# LB_BIT_i36_MICROSEQUENCER-v03_6_7.net
KiCad netlist of a schematic drawn in EAGLE
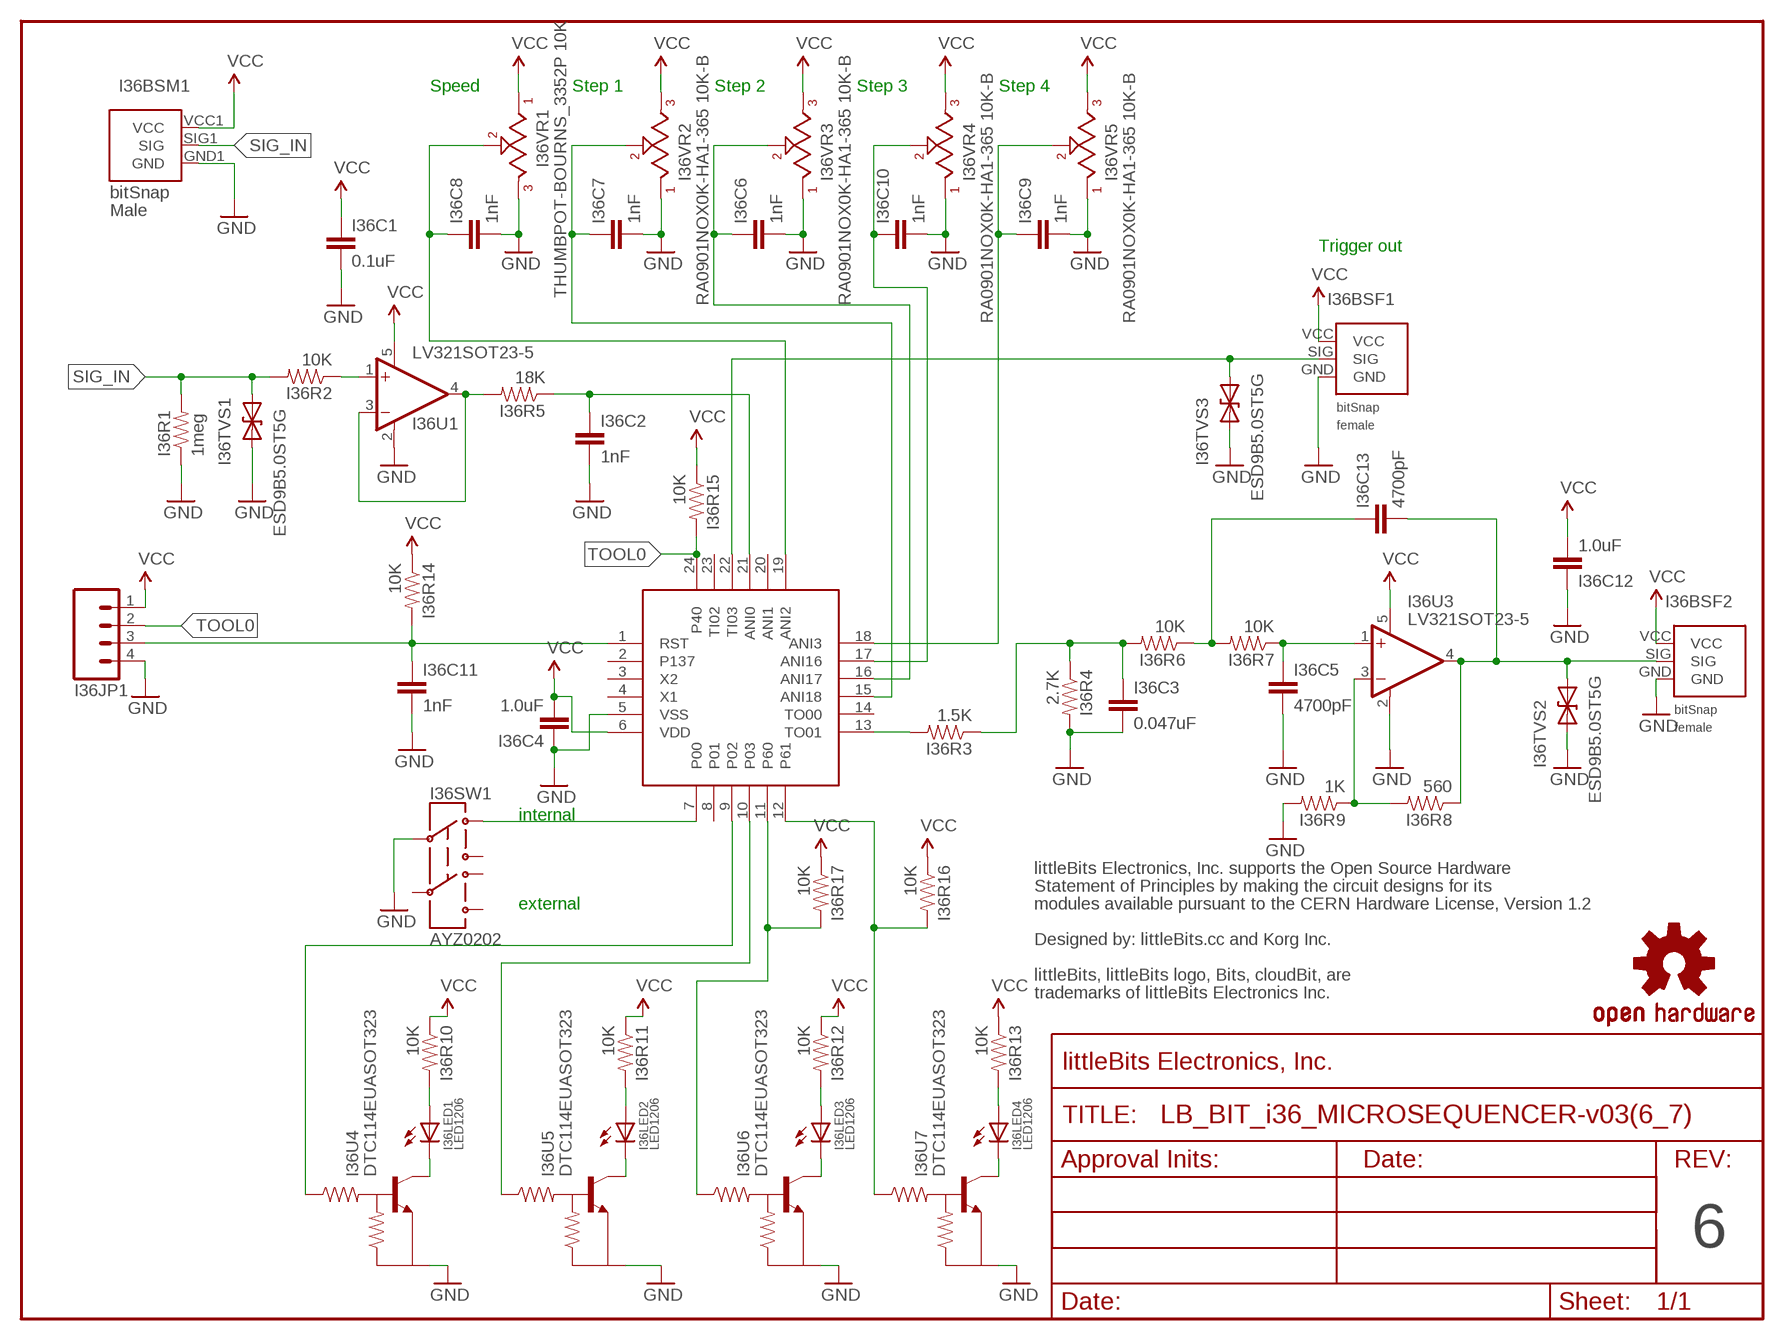
[diagram p0: schematic, sheet 1]

(export (version "E")
  (design (tool "Eeschema 10.0.6"))
  (components
    (comp (ref "I36BSF1")
      (value "BITSNAP_V03_FEMALE")
      (footprint "eagle-import:BITSNAP_V03_FEMALE")
      (libsource (lib "eagle-import") (part "BITSNAP_V03_FEMALE"))
    )
    (comp (ref "I36BSF2")
      (value "BITSNAP_V03_FEMALE")
      (footprint "eagle-import:BITSNAP_V03_FEMALE")
      (libsource (lib "eagle-import") (part "BITSNAP_V03_FEMALE"))
    )
    (comp (ref "I36BSM1")
      (value "BITSNAP_V03_MALE")
      (footprint "eagle-import:BITSNAP_V03_MALE")
      (libsource (lib "eagle-import") (part "BITSNAP_V03_MALE"))
    )
    (comp (ref "I36C1")
      (value "0.1uF")
      (footprint "eagle-import:CAP-0603")
      (libsource (lib "eagle-import") (part "CAPCAP-0603"))
    )
    (comp (ref "I36C2")
      (value "1nF")
      (footprint "eagle-import:CAP-0603")
      (libsource (lib "eagle-import") (part "CAPCAP-0603"))
    )
    (comp (ref "I36C3")
      (value "0.047uF")
      (footprint "eagle-import:CAP-0603")
      (libsource (lib "eagle-import") (part "CAPCAP-0603"))
    )
    (comp (ref "I36C4")
      (value "1.0uF")
      (footprint "eagle-import:CAP-0603")
      (libsource (lib "eagle-import") (part "CAPCAP-0603"))
    )
    (comp (ref "I36C5")
      (value "4700pF")
      (footprint "eagle-import:CAP-0603")
      (libsource (lib "eagle-import") (part "CAPCAP-0603"))
    )
    (comp (ref "I36C6")
      (value "1nF")
      (footprint "eagle-import:CAP-0603")
      (libsource (lib "eagle-import") (part "CAPCAP-0603"))
    )
    (comp (ref "I36C7")
      (value "1nF")
      (footprint "eagle-import:CAP-0603")
      (libsource (lib "eagle-import") (part "CAPCAP-0603"))
    )
    (comp (ref "I36C8")
      (value "1nF")
      (footprint "eagle-import:CAP-0603")
      (libsource (lib "eagle-import") (part "CAPCAP-0603"))
    )
    (comp (ref "I36C9")
      (value "1nF")
      (footprint "eagle-import:CAP-0603")
      (libsource (lib "eagle-import") (part "CAPCAP-0603"))
    )
    (comp (ref "I36C10")
      (value "1nF")
      (footprint "eagle-import:CAP-0603")
      (libsource (lib "eagle-import") (part "CAPCAP-0603"))
    )
    (comp (ref "I36C11")
      (value "1nF")
      (footprint "eagle-import:CAP-0603")
      (libsource (lib "eagle-import") (part "CAPCAP-0603"))
    )
    (comp (ref "I36C12")
      (value "1.0uF")
      (footprint "eagle-import:CAP-0603")
      (libsource (lib "eagle-import") (part "CAPCAP-0603"))
    )
    (comp (ref "I36C13")
      (value "4700pF")
      (footprint "eagle-import:CAP-0603")
      (libsource (lib "eagle-import") (part "CAPCAP-0603"))
    )
    (comp (ref "I36JP1")
      (value "HDR-4SM_SML")
      (footprint "eagle-import:SIP4-SM-0.1IN-NOS.S.")
      (libsource (lib "eagle-import") (part "HDR-4SM_SML"))
    )
    (comp (ref "I36LED1")
      (value "LED1206")
      (footprint "eagle-import:LED-1206")
      (libsource (lib "eagle-import") (part "LED1206"))
    )
    (comp (ref "I36LED2")
      (value "LED1206")
      (footprint "eagle-import:LED-1206")
      (libsource (lib "eagle-import") (part "LED1206"))
    )
    (comp (ref "I36LED3")
      (value "LED1206")
      (footprint "eagle-import:LED-1206")
      (libsource (lib "eagle-import") (part "LED1206"))
    )
    (comp (ref "I36LED4")
      (value "LED1206")
      (footprint "eagle-import:LED-1206")
      (libsource (lib "eagle-import") (part "LED1206"))
    )
    (comp (ref "I36R1")
      (value "1meg")
      (footprint "eagle-import:RES-0603")
      (libsource (lib "eagle-import") (part "RESISTOR0603"))
    )
    (comp (ref "I36R2")
      (value "10K")
      (footprint "eagle-import:RES-0603")
      (libsource (lib "eagle-import") (part "RESISTOR0603"))
    )
    (comp (ref "I36R3")
      (value "1.5K")
      (footprint "eagle-import:RES-0603")
      (libsource (lib "eagle-import") (part "RESISTOR0603"))
    )
    (comp (ref "I36R4")
      (value "2.7K")
      (footprint "eagle-import:RES-0603")
      (libsource (lib "eagle-import") (part "RESISTOR0603"))
    )
    (comp (ref "I36R5")
      (value "18K")
      (footprint "eagle-import:RES-0603")
      (libsource (lib "eagle-import") (part "RESISTOR0603"))
    )
    (comp (ref "I36R6")
      (value "10K")
      (footprint "eagle-import:RES-0603")
      (libsource (lib "eagle-import") (part "RESISTOR0603"))
    )
    (comp (ref "I36R7")
      (value "10K")
      (footprint "eagle-import:RES-0603")
      (libsource (lib "eagle-import") (part "RESISTOR0603"))
    )
    (comp (ref "I36R8")
      (value "560")
      (footprint "eagle-import:RES-0603")
      (libsource (lib "eagle-import") (part "RESISTOR0603"))
    )
    (comp (ref "I36R9")
      (value "1K")
      (footprint "eagle-import:RES-0603")
      (libsource (lib "eagle-import") (part "RESISTOR0603"))
    )
    (comp (ref "I36R10")
      (value "10K")
      (footprint "eagle-import:RES-0603")
      (libsource (lib "eagle-import") (part "RESISTOR0603"))
    )
    (comp (ref "I36R11")
      (value "10K")
      (footprint "eagle-import:RES-0603")
      (libsource (lib "eagle-import") (part "RESISTOR0603"))
    )
    (comp (ref "I36R12")
      (value "10K")
      (footprint "eagle-import:RES-0603")
      (libsource (lib "eagle-import") (part "RESISTOR0603"))
    )
    (comp (ref "I36R13")
      (value "10K")
      (footprint "eagle-import:RES-0603")
      (libsource (lib "eagle-import") (part "RESISTOR0603"))
    )
    (comp (ref "I36R14")
      (value "10K")
      (footprint "eagle-import:RES-0603")
      (libsource (lib "eagle-import") (part "RESISTOR0603"))
    )
    (comp (ref "I36R15")
      (value "10K")
      (footprint "eagle-import:RES-0603")
      (libsource (lib "eagle-import") (part "RESISTOR0603"))
    )
    (comp (ref "I36R16")
      (value "10K")
      (footprint "eagle-import:RES-0603")
      (libsource (lib "eagle-import") (part "RESISTOR0603"))
    )
    (comp (ref "I36R17")
      (value "10K")
      (footprint "eagle-import:RES-0603")
      (libsource (lib "eagle-import") (part "RESISTOR0603"))
    )
    (comp (ref "I36SW1")
      (value "AYZ0202")
      (footprint "eagle-import:AYZ0202")
      (libsource (lib "eagle-import") (part "AYZ0202"))
    )
    (comp (ref "I36TVS1")
      (value "ESD9B5.0ST5G")
      (footprint "eagle-import:SOD-923")
      (libsource (lib "eagle-import") (part "DIODE-TVSSOD-923"))
    )
    (comp (ref "I36TVS2")
      (value "ESD9B5.0ST5G")
      (footprint "eagle-import:SOD-923")
      (libsource (lib "eagle-import") (part "DIODE-TVSSOD-923"))
    )
    (comp (ref "I36TVS3")
      (value "ESD9B5.0ST5G")
      (footprint "eagle-import:SOD-923")
      (libsource (lib "eagle-import") (part "DIODE-TVSSOD-923"))
    )
    (comp (ref "I36U1")
      (value "LV321SOT23-5")
      (footprint "eagle-import:SOT23-5")
      (libsource (lib "eagle-import") (part "LV321SOT23-5"))
    )
    (comp (ref "I36U2")
      (value "R5F10278QFN-24")
      (footprint "eagle-import:QFN-24(4MM)")
      (libsource (lib "eagle-import") (part "R5F10278QFN-24"))
    )
    (comp (ref "I36U3")
      (value "LV321SOT23-5")
      (footprint "eagle-import:SOT23-5")
      (libsource (lib "eagle-import") (part "LV321SOT23-5"))
    )
    (comp (ref "I36U4")
      (value "DTC114EUASOT323")
      (footprint "eagle-import:SOT323")
      (libsource (lib "eagle-import") (part "DTC114EUASOT323"))
    )
    (comp (ref "I36U5")
      (value "DTC114EUASOT323")
      (footprint "eagle-import:SOT323")
      (libsource (lib "eagle-import") (part "DTC114EUASOT323"))
    )
    (comp (ref "I36U6")
      (value "DTC114EUASOT323")
      (footprint "eagle-import:SOT323")
      (libsource (lib "eagle-import") (part "DTC114EUASOT323"))
    )
    (comp (ref "I36U7")
      (value "DTC114EUASOT323")
      (footprint "eagle-import:SOT323")
      (libsource (lib "eagle-import") (part "DTC114EUASOT323"))
    )
    (comp (ref "I36VR1")
      (value "THUMBPOT-BOURNS_3352P 10K")
      (footprint "eagle-import:THUMBPOT-BOURNS_3352")
      (libsource (lib "eagle-import") (part "THUMBPOT-BOURNS_3352P"))
    )
    (comp (ref "I36VR2")
      (value "RA0901NOX0K-HA1-365 10K-B")
      (footprint "eagle-import:ALPS_POT")
      (libsource (lib "eagle-import") (part "ALPS_POTTH"))
    )
    (comp (ref "I36VR3")
      (value "RA0901NOX0K-HA1-365 10K-B")
      (footprint "eagle-import:ALPS_POT")
      (libsource (lib "eagle-import") (part "ALPS_POTTH"))
    )
    (comp (ref "I36VR4")
      (value "RA0901NOX0K-HA1-365 10K-B")
      (footprint "eagle-import:ALPS_POT")
      (libsource (lib "eagle-import") (part "ALPS_POTTH"))
    )
    (comp (ref "I36VR5")
      (value "RA0901NOX0K-HA1-365 10K-B")
      (footprint "eagle-import:ALPS_POT")
      (libsource (lib "eagle-import") (part "ALPS_POTTH"))
    )
    (comp (ref "U$1")
      (value "OSHWCREDIT-KORG")
      (footprint "eagle-import:OSHWCREDIT-KORG")
      (libsource (lib "eagle-import") (part "OSHWCREDIT-KORG"))
    )
    (comp (ref "U$2")
      (value "OSHW-LOGOL")
      (footprint "eagle-import:OSHW-LOGO-L")
      (libsource (lib "eagle-import") (part "OSHW-LOGOL"))
    )
    (comp (ref "U$3")
      (value "FRAME-LETTER-OHWOHW")
      (footprint "eagle-import:FABDWG01-OHW")
      (libsource (lib "eagle-import") (part "FRAME-LETTER-OHWOHW"))
    )
  )
  (nets
    (net (code "1") (name "GND") (class "Default")
      (node (ref "I36BSF1") (pin "GND") (pinfunction "GND_GND") (pintype "bidirectional"))
      (node (ref "I36BSF2") (pin "GND") (pinfunction "GND_GND") (pintype "bidirectional"))
      (node (ref "I36BSM1") (pin "GND1") (pinfunction "GND_GND1") (pintype "bidirectional"))
      (node (ref "I36C1") (pin "2") (pinfunction "2_2") (pintype "passive"))
      (node (ref "I36C10") (pin "2") (pinfunction "2_2") (pintype "passive"))
      (node (ref "I36C11") (pin "2") (pinfunction "2_2") (pintype "passive"))
      (node (ref "I36C12") (pin "1") (pinfunction "1_1") (pintype "passive"))
      (node (ref "I36C2") (pin "2") (pinfunction "2_2") (pintype "passive"))
      (node (ref "I36C3") (pin "2") (pinfunction "2_2") (pintype "passive"))
      (node (ref "I36C4") (pin "1") (pinfunction "1_1") (pintype "passive"))
      (node (ref "I36C5") (pin "2") (pinfunction "2_2") (pintype "passive"))
      (node (ref "I36C6") (pin "2") (pinfunction "2_2") (pintype "passive"))
      (node (ref "I36C7") (pin "2") (pinfunction "2_2") (pintype "passive"))
      (node (ref "I36C8") (pin "2") (pinfunction "2_2") (pintype "passive"))
      (node (ref "I36C9") (pin "2") (pinfunction "2_2") (pintype "passive"))
      (node (ref "I36JP1") (pin "4") (pinfunction "4_4") (pintype "passive"))
      (node (ref "I36R1") (pin "1") (pinfunction "1_1") (pintype "passive"))
      (node (ref "I36R4") (pin "2") (pinfunction "2_2") (pintype "passive"))
      (node (ref "I36R9") (pin "2") (pinfunction "2_2") (pintype "passive"))
      (node (ref "I36SW1") (pin "2") (pinfunction "2_2") (pintype "bidirectional"))
      (node (ref "I36TVS1") (pin "1") (pinfunction "A_1") (pintype "passive"))
      (node (ref "I36TVS2") (pin "1") (pinfunction "A_1") (pintype "passive"))
      (node (ref "I36TVS3") (pin "1") (pinfunction "A_1") (pintype "passive"))
      (node (ref "I36U1") (pin "2") (pinfunction "V-_2") (pintype "power_in"))
      (node (ref "I36U2") (pin "5") (pinfunction "VSS_5") (pintype "bidirectional"))
      (node (ref "I36U3") (pin "2") (pinfunction "V-_2") (pintype "power_in"))
      (node (ref "I36U4") (pin "GND") (pinfunction "E_GND") (pintype "passive"))
      (node (ref "I36U5") (pin "GND") (pinfunction "E_GND") (pintype "passive"))
      (node (ref "I36U6") (pin "GND") (pinfunction "E_GND") (pintype "passive"))
      (node (ref "I36U7") (pin "GND") (pinfunction "E_GND") (pintype "passive"))
      (node (ref "I36VR1") (pin "1") (pinfunction "3_1") (pintype "passive"))
      (node (ref "I36VR2") (pin "1") (pinfunction "1_1") (pintype "passive"))
      (node (ref "I36VR3") (pin "1") (pinfunction "1_1") (pintype "passive"))
      (node (ref "I36VR4") (pin "1") (pinfunction "1_1") (pintype "passive"))
      (node (ref "I36VR5") (pin "1") (pinfunction "1_1") (pintype "passive"))
    )
    (net (code "2") (name "Net-(I36C3-Pad1)") (class "Default")
      (node (ref "I36C3") (pin "1") (pinfunction "1_1") (pintype "passive"))
      (node (ref "I36R3") (pin "1") (pinfunction "1_1") (pintype "passive"))
      (node (ref "I36R4") (pin "1") (pinfunction "1_1") (pintype "passive"))
      (node (ref "I36R6") (pin "2") (pinfunction "2_2") (pintype "passive"))
    )
    (net (code "3") (name "Net-(I36C13-Pad1)") (class "Default")
      (node (ref "I36C13") (pin "1") (pinfunction "1_1") (pintype "passive"))
      (node (ref "I36R6") (pin "1") (pinfunction "1_1") (pintype "passive"))
      (node (ref "I36R7") (pin "2") (pinfunction "2_2") (pintype "passive"))
    )
    (net (code "4") (name "Net-(I36LED1-PadA)") (class "Default")
      (node (ref "I36LED1") (pin "A") (pinfunction "A_A") (pintype "passive"))
      (node (ref "I36R10") (pin "2") (pinfunction "2_2") (pintype "passive"))
    )
    (net (code "5") (name "Net-(I36LED2-PadA)") (class "Default")
      (node (ref "I36LED2") (pin "A") (pinfunction "A_A") (pintype "passive"))
      (node (ref "I36R11") (pin "2") (pinfunction "2_2") (pintype "passive"))
    )
    (net (code "6") (name "Net-(I36LED3-PadA)") (class "Default")
      (node (ref "I36LED3") (pin "A") (pinfunction "A_A") (pintype "passive"))
      (node (ref "I36R12") (pin "2") (pinfunction "2_2") (pintype "passive"))
    )
    (net (code "7") (name "Net-(I36LED4-PadA)") (class "Default")
      (node (ref "I36LED4") (pin "A") (pinfunction "A_A") (pintype "passive"))
      (node (ref "I36R13") (pin "2") (pinfunction "2_2") (pintype "passive"))
    )
    (net (code "8") (name "Net-(I36TVS2-C)") (class "Default")
      (node (ref "I36BSF2") (pin "SIG") (pinfunction "SIG_SIG") (pintype "bidirectional"))
      (node (ref "I36C13") (pin "2") (pinfunction "2_2") (pintype "passive"))
      (node (ref "I36R8") (pin "1") (pinfunction "1_1") (pintype "passive"))
      (node (ref "I36TVS2") (pin "2") (pinfunction "C_2") (pintype "passive"))
      (node (ref "I36U3") (pin "4") (pinfunction "OUT_4") (pintype "output"))
    )
    (net (code "9") (name "Net-(I36TVS3-C)") (class "Default")
      (node (ref "I36BSF1") (pin "SIG") (pinfunction "SIG_SIG") (pintype "bidirectional"))
      (node (ref "I36TVS3") (pin "2") (pinfunction "C_2") (pintype "passive"))
      (node (ref "I36U2") (pin "22") (pinfunction "TI03_22") (pintype "bidirectional"))
    )
    (net (code "10") (name "Net-(I36U1-+IN)") (class "Default")
      (node (ref "I36R2") (pin "1") (pinfunction "1_1") (pintype "passive"))
      (node (ref "I36U1") (pin "1") (pinfunction "+IN_1") (pintype "input"))
    )
    (net (code "11") (name "Net-(I36U1--IN)") (class "Default")
      (node (ref "I36R5") (pin "2") (pinfunction "2_2") (pintype "passive"))
      (node (ref "I36U1") (pin "3") (pinfunction "-IN_3") (pintype "input"))
      (node (ref "I36U1") (pin "4") (pinfunction "OUT_4") (pintype "output"))
    )
    (net (code "12") (name "Net-(I36U2-ANI0)") (class "Default")
      (node (ref "I36C2") (pin "1") (pinfunction "1_1") (pintype "passive"))
      (node (ref "I36R5") (pin "1") (pinfunction "1_1") (pintype "passive"))
      (node (ref "I36U2") (pin "21") (pinfunction "ANI0_21") (pintype "bidirectional"))
    )
    (net (code "13") (name "Net-(I36U2-ANI2)") (class "Default")
      (node (ref "I36C8") (pin "1") (pinfunction "1_1") (pintype "passive"))
      (node (ref "I36U2") (pin "19") (pinfunction "ANI2_19") (pintype "bidirectional"))
      (node (ref "I36VR1") (pin "2") (pinfunction "2_2") (pintype "passive"))
    )
    (net (code "14") (name "Net-(I36U2-ANI3)") (class "Default")
      (node (ref "I36C9") (pin "1") (pinfunction "1_1") (pintype "passive"))
      (node (ref "I36U2") (pin "18") (pinfunction "ANI3_18") (pintype "bidirectional"))
      (node (ref "I36VR5") (pin "2") (pinfunction "2_2") (pintype "passive"))
    )
    (net (code "15") (name "Net-(I36U2-ANI16)") (class "Default")
      (node (ref "I36C10") (pin "1") (pinfunction "1_1") (pintype "passive"))
      (node (ref "I36U2") (pin "17") (pinfunction "ANI16_17") (pintype "bidirectional"))
      (node (ref "I36VR4") (pin "2") (pinfunction "2_2") (pintype "passive"))
    )
    (net (code "16") (name "Net-(I36U2-ANI17)") (class "Default")
      (node (ref "I36C6") (pin "1") (pinfunction "1_1") (pintype "passive"))
      (node (ref "I36U2") (pin "16") (pinfunction "ANI17_16") (pintype "bidirectional"))
      (node (ref "I36VR3") (pin "2") (pinfunction "2_2") (pintype "passive"))
    )
    (net (code "17") (name "Net-(I36U2-ANI18)") (class "Default")
      (node (ref "I36C7") (pin "1") (pinfunction "1_1") (pintype "passive"))
      (node (ref "I36U2") (pin "15") (pinfunction "ANI18_15") (pintype "bidirectional"))
      (node (ref "I36VR2") (pin "2") (pinfunction "2_2") (pintype "passive"))
    )
    (net (code "18") (name "Net-(I36U2-P00)") (class "Default")
      (node (ref "I36SW1") (pin "1") (pinfunction "1_1") (pintype "bidirectional"))
      (node (ref "I36U2") (pin "7") (pinfunction "P00_7") (pintype "bidirectional"))
    )
    (net (code "19") (name "Net-(I36U2-P02)") (class "Default")
      (node (ref "I36U2") (pin "9") (pinfunction "P02_9") (pintype "bidirectional"))
      (node (ref "I36U4") (pin "IN") (pinfunction "1_IN") (pintype "passive"))
    )
    (net (code "20") (name "Net-(I36U2-P03)") (class "Default")
      (node (ref "I36U2") (pin "10") (pinfunction "P03_10") (pintype "bidirectional"))
      (node (ref "I36U5") (pin "IN") (pinfunction "1_IN") (pintype "passive"))
    )
    (net (code "21") (name "Net-(I36U2-P60)") (class "Default")
      (node (ref "I36R17") (pin "2") (pinfunction "2_2") (pintype "passive"))
      (node (ref "I36U2") (pin "11") (pinfunction "P60_11") (pintype "bidirectional"))
      (node (ref "I36U6") (pin "IN") (pinfunction "1_IN") (pintype "passive"))
    )
    (net (code "22") (name "Net-(I36U2-P61)") (class "Default")
      (node (ref "I36R16") (pin "2") (pinfunction "2_2") (pintype "passive"))
      (node (ref "I36U2") (pin "12") (pinfunction "P61_12") (pintype "bidirectional"))
      (node (ref "I36U7") (pin "IN") (pinfunction "1_IN") (pintype "passive"))
    )
    (net (code "23") (name "Net-(I36U2-RST)") (class "Default")
      (node (ref "I36C11") (pin "1") (pinfunction "1_1") (pintype "passive"))
      (node (ref "I36JP1") (pin "3") (pinfunction "3_3") (pintype "passive"))
      (node (ref "I36R14") (pin "2") (pinfunction "2_2") (pintype "passive"))
      (node (ref "I36U2") (pin "1") (pinfunction "RST_1") (pintype "bidirectional"))
    )
    (net (code "24") (name "Net-(I36U2-TO01)") (class "Default")
      (node (ref "I36R3") (pin "2") (pinfunction "2_2") (pintype "passive"))
      (node (ref "I36U2") (pin "13") (pinfunction "TO01_13") (pintype "bidirectional"))
    )
    (net (code "25") (name "Net-(I36U3-+IN)") (class "Default")
      (node (ref "I36C5") (pin "1") (pinfunction "1_1") (pintype "passive"))
      (node (ref "I36R7") (pin "1") (pinfunction "1_1") (pintype "passive"))
      (node (ref "I36U3") (pin "1") (pinfunction "+IN_1") (pintype "input"))
    )
    (net (code "26") (name "Net-(I36U3--IN)") (class "Default")
      (node (ref "I36R8") (pin "2") (pinfunction "2_2") (pintype "passive"))
      (node (ref "I36R9") (pin "1") (pinfunction "1_1") (pintype "passive"))
      (node (ref "I36U3") (pin "3") (pinfunction "-IN_3") (pintype "input"))
    )
    (net (code "27") (name "Net-(I36U4-C)") (class "Default")
      (node (ref "I36LED1") (pin "C") (pinfunction "C_C") (pintype "passive"))
      (node (ref "I36U4") (pin "OUT") (pinfunction "C_OUT") (pintype "passive"))
    )
    (net (code "28") (name "Net-(I36U5-C)") (class "Default")
      (node (ref "I36LED2") (pin "C") (pinfunction "C_C") (pintype "passive"))
      (node (ref "I36U5") (pin "OUT") (pinfunction "C_OUT") (pintype "passive"))
    )
    (net (code "29") (name "Net-(I36U6-C)") (class "Default")
      (node (ref "I36LED3") (pin "C") (pinfunction "C_C") (pintype "passive"))
      (node (ref "I36U6") (pin "OUT") (pinfunction "C_OUT") (pintype "passive"))
    )
    (net (code "30") (name "Net-(I36U7-C)") (class "Default")
      (node (ref "I36LED4") (pin "C") (pinfunction "C_C") (pintype "passive"))
      (node (ref "I36U7") (pin "OUT") (pinfunction "C_OUT") (pintype "passive"))
    )
    (net (code "31") (name "SIG_IN") (class "Default")
      (node (ref "I36BSM1") (pin "SIG1") (pinfunction "SIG_SIG1") (pintype "bidirectional"))
      (node (ref "I36R1") (pin "2") (pinfunction "2_2") (pintype "passive"))
      (node (ref "I36R2") (pin "2") (pinfunction "2_2") (pintype "passive"))
      (node (ref "I36TVS1") (pin "2") (pinfunction "C_2") (pintype "passive"))
    )
    (net (code "32") (name "TOOL0") (class "Default")
      (node (ref "I36JP1") (pin "2") (pinfunction "2_2") (pintype "passive"))
      (node (ref "I36R15") (pin "2") (pinfunction "2_2") (pintype "passive"))
      (node (ref "I36U2") (pin "24") (pinfunction "P40_24") (pintype "bidirectional"))
    )
    (net (code "33") (name "VCC") (class "Default")
      (node (ref "I36BSF1") (pin "VCC") (pinfunction "VCC_VCC") (pintype "bidirectional"))
      (node (ref "I36BSF2") (pin "VCC") (pinfunction "VCC_VCC") (pintype "bidirectional"))
      (node (ref "I36BSM1") (pin "VCC1") (pinfunction "VCC_VCC1") (pintype "bidirectional"))
      (node (ref "I36C1") (pin "1") (pinfunction "1_1") (pintype "passive"))
      (node (ref "I36C12") (pin "2") (pinfunction "2_2") (pintype "passive"))
      (node (ref "I36C4") (pin "2") (pinfunction "2_2") (pintype "passive"))
      (node (ref "I36JP1") (pin "1") (pinfunction "1_1") (pintype "passive"))
      (node (ref "I36R10") (pin "1") (pinfunction "1_1") (pintype "passive"))
      (node (ref "I36R11") (pin "1") (pinfunction "1_1") (pintype "passive"))
      (node (ref "I36R12") (pin "1") (pinfunction "1_1") (pintype "passive"))
      (node (ref "I36R13") (pin "1") (pinfunction "1_1") (pintype "passive"))
      (node (ref "I36R14") (pin "1") (pinfunction "1_1") (pintype "passive"))
      (node (ref "I36R15") (pin "1") (pinfunction "1_1") (pintype "passive"))
      (node (ref "I36R16") (pin "1") (pinfunction "1_1") (pintype "passive"))
      (node (ref "I36R17") (pin "1") (pinfunction "1_1") (pintype "passive"))
      (node (ref "I36U1") (pin "5") (pinfunction "V+_5") (pintype "power_in"))
      (node (ref "I36U2") (pin "6") (pinfunction "VDD_6") (pintype "bidirectional"))
      (node (ref "I36U3") (pin "5") (pinfunction "V+_5") (pintype "power_in"))
      (node (ref "I36VR1") (pin "3") (pinfunction "1_3") (pintype "passive"))
      (node (ref "I36VR2") (pin "3") (pinfunction "3_3") (pintype "passive"))
      (node (ref "I36VR3") (pin "3") (pinfunction "3_3") (pintype "passive"))
      (node (ref "I36VR4") (pin "3") (pinfunction "3_3") (pintype "passive"))
      (node (ref "I36VR5") (pin "3") (pinfunction "3_3") (pintype "passive"))
    )
    (net (code "34") (name "unconnected-(I36SW1-Pad3)") (class "Default")
      (node (ref "I36SW1") (pin "3") (pinfunction "3_3") (pintype "bidirectional"))
    )
    (net (code "35") (name "unconnected-(I36SW1-Pad4)") (class "Default")
      (node (ref "I36SW1") (pin "4") (pinfunction "4_4") (pintype "bidirectional"))
    )
    (net (code "36") (name "unconnected-(I36SW1-Pad5)") (class "Default")
      (node (ref "I36SW1") (pin "5") (pinfunction "5_5") (pintype "bidirectional"))
    )
    (net (code "37") (name "unconnected-(I36SW1-Pad6)") (class "Default")
      (node (ref "I36SW1") (pin "6") (pinfunction "6_6") (pintype "bidirectional"))
    )
    (net (code "38") (name "unconnected-(I36U2-ANI1-Pad20)") (class "Default")
      (node (ref "I36U2") (pin "20") (pinfunction "ANI1_20") (pintype "bidirectional"))
    )
    (net (code "39") (name "unconnected-(I36U2-P01-Pad8)") (class "Default")
      (node (ref "I36U2") (pin "8") (pinfunction "P01_8") (pintype "bidirectional"))
    )
    (net (code "40") (name "unconnected-(I36U2-P137-Pad2)") (class "Default")
      (node (ref "I36U2") (pin "2") (pinfunction "P137_2") (pintype "bidirectional"))
    )
    (net (code "41") (name "unconnected-(I36U2-TI02-Pad23)") (class "Default")
      (node (ref "I36U2") (pin "23") (pinfunction "TI02_23") (pintype "bidirectional"))
    )
    (net (code "42") (name "unconnected-(I36U2-TO00-Pad14)") (class "Default")
      (node (ref "I36U2") (pin "14") (pinfunction "TO00_14") (pintype "bidirectional"))
    )
    (net (code "43") (name "unconnected-(I36U2-X1-Pad4)") (class "Default")
      (node (ref "I36U2") (pin "4") (pinfunction "X1_4") (pintype "bidirectional"))
    )
    (net (code "44") (name "unconnected-(I36U2-X2-Pad3)") (class "Default")
      (node (ref "I36U2") (pin "3") (pinfunction "X2_3") (pintype "bidirectional"))
    )
  )
)
